# design.net
KiCad netlist of a schematic drawn in Altium Designer
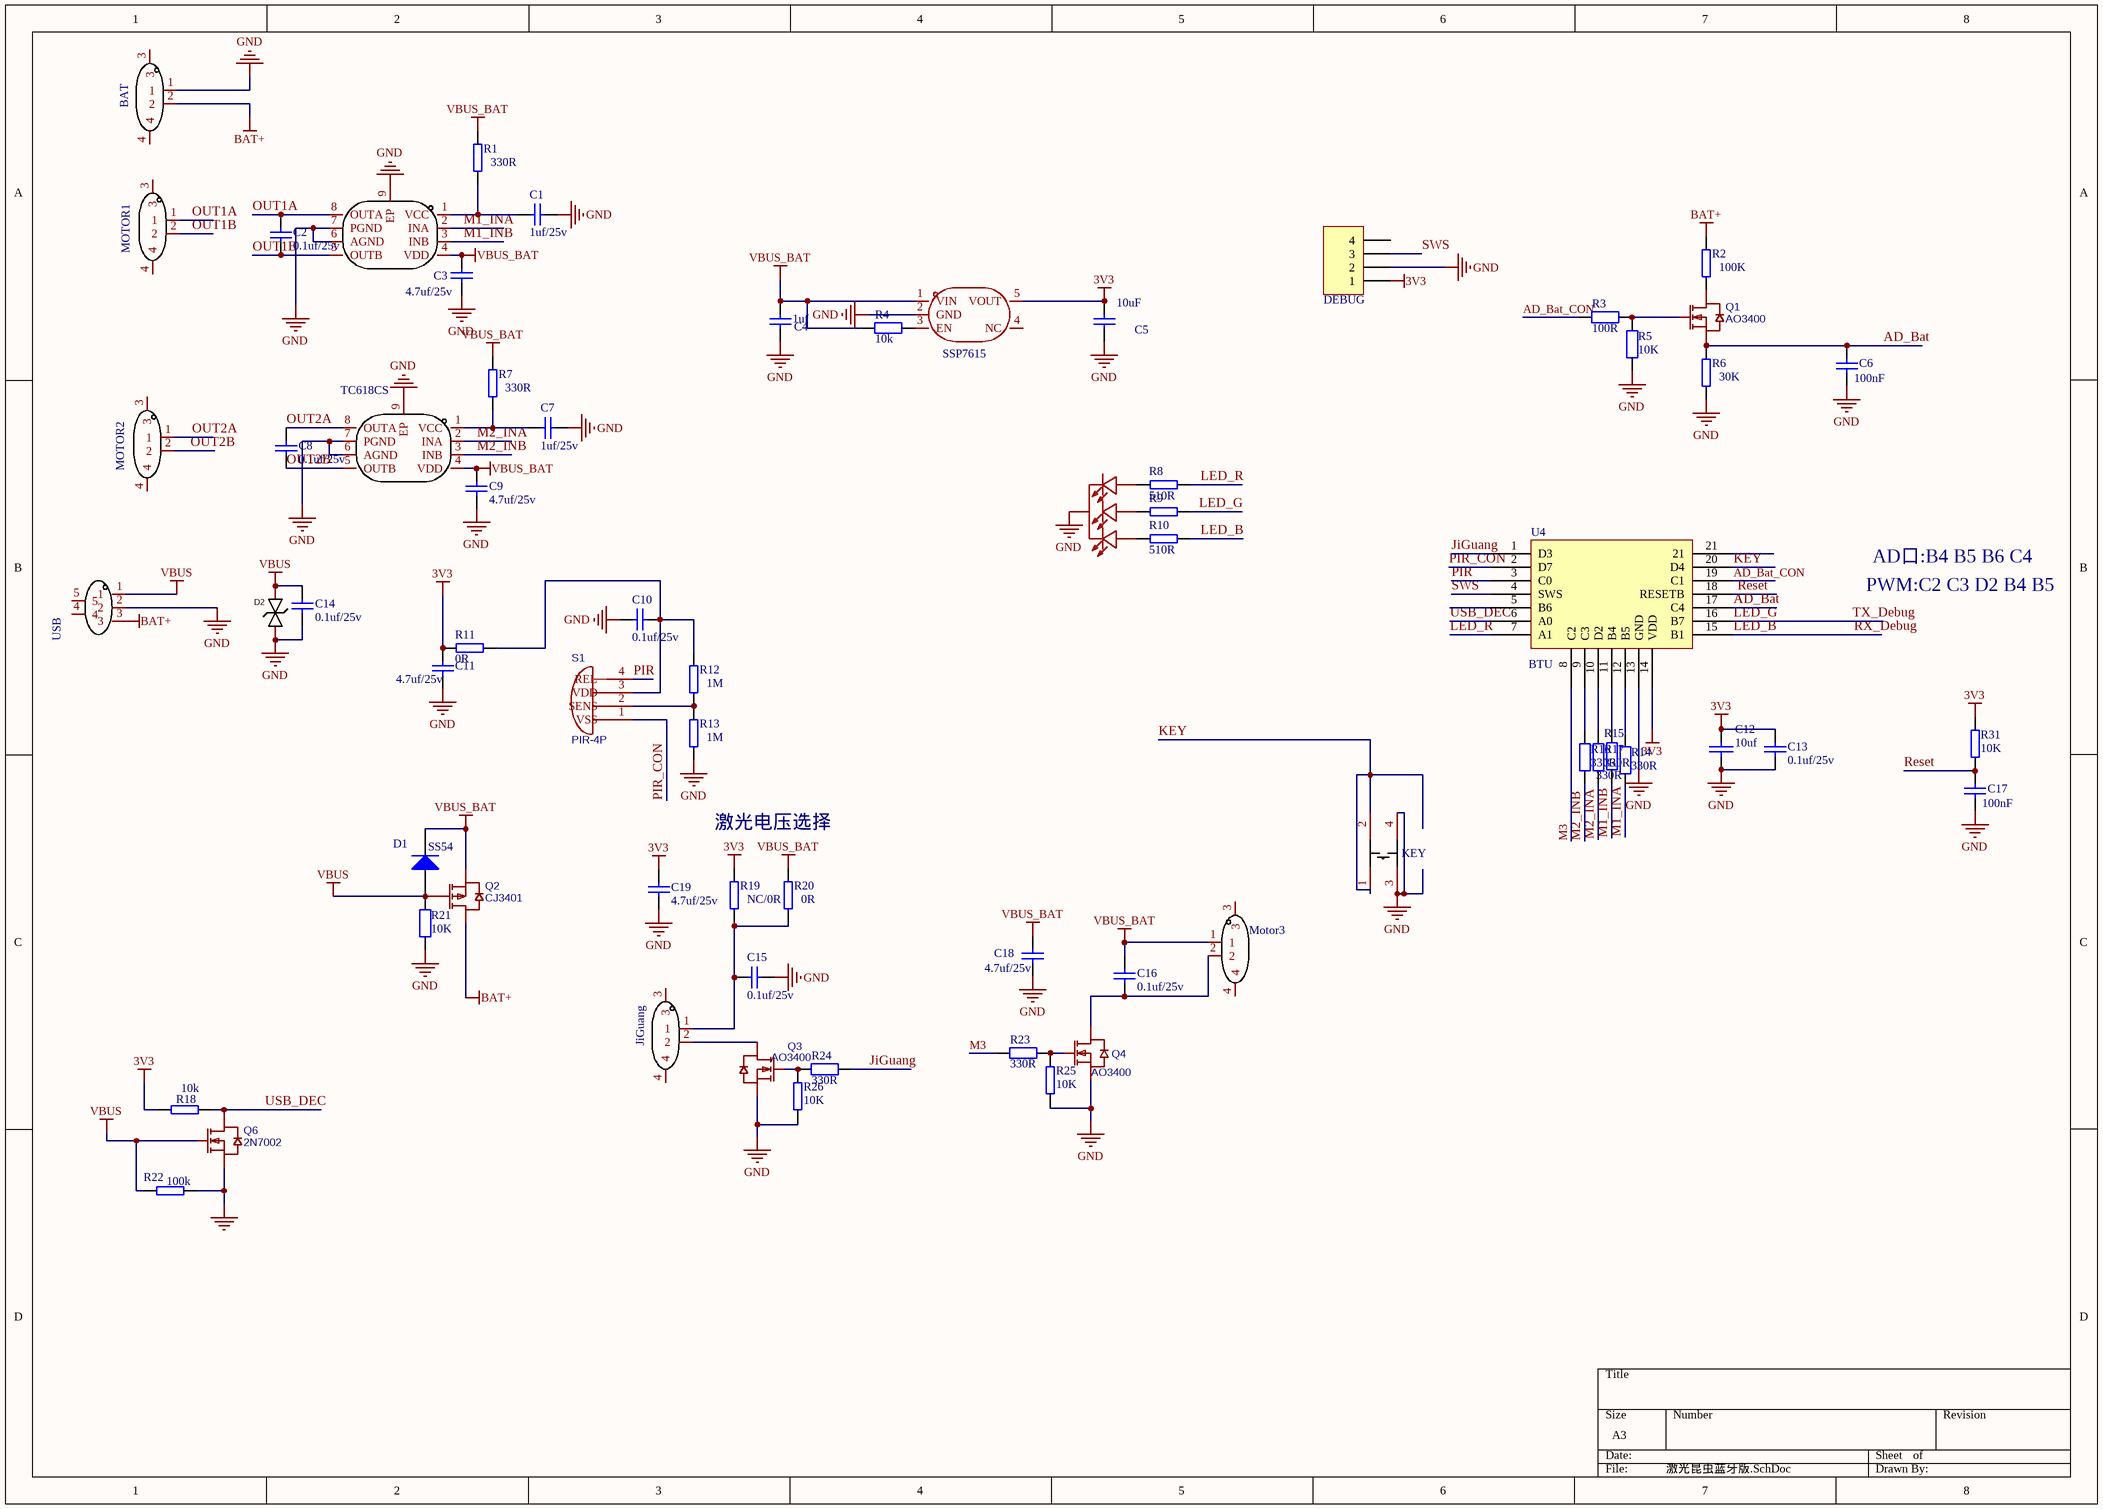
[diagram p0: 激光昆虫蓝牙版.SchDoc]

(export (version "E")
  (design (tool "Eeschema 10.0.6"))
  (components
    (comp (ref "C1")
      (value "1uf/25v")
      (footprint "0603_C")
      (description "Capacitor")
      (fields (field (name "PUBLISHER") "Altium Limited"))
      (libsource (lib "*") (part "Cap"))
    )
    (comp (ref "C2")
      (value "0.1uf/25v")
      (footprint "0603_C")
      (description "Capacitor")
      (fields (field (name "PUBLISHER") "Altium Limited"))
      (libsource (lib "*") (part "Cap"))
    )
    (comp (ref "C3")
      (value "4.7uf/25v")
      (footprint "0603_C")
      (description "Capacitor")
      (fields (field (name "PUBLISHER") "Altium Limited"))
      (libsource (lib "*") (part "Cap"))
    )
    (comp (ref "C4")
      (value "1uf")
      (footprint "0603_C")
      (description "无极电容")
      (libsource (lib "电容电阻电感保险") (part "Cap1"))
    )
    (comp (ref "C5")
      (value "10uF")
      (footprint "0603_C")
      (description "Capacitor")
      (fields (field (name "PUBLISHER") "Altium Limited"))
      (libsource (lib "*") (part "Cap"))
    )
    (comp (ref "C6") (value "100nF") (footprint "0603_C") (libsource (lib "DIY") (part "CAP")))
    (comp (ref "C7")
      (value "1uf/25v")
      (footprint "0603_C")
      (description "Capacitor")
      (fields (field (name "PUBLISHER") "Altium Limited"))
      (libsource (lib "*") (part "Cap"))
    )
    (comp (ref "C8")
      (value "0.1uf/25v")
      (footprint "0603_C")
      (description "Capacitor")
      (fields (field (name "PUBLISHER") "Altium Limited"))
      (libsource (lib "*") (part "Cap"))
    )
    (comp (ref "C9")
      (value "4.7uf/25v")
      (footprint "0603_C")
      (description "Capacitor")
      (fields (field (name "PUBLISHER") "Altium Limited"))
      (libsource (lib "*") (part "Cap"))
    )
    (comp (ref "C10")
      (value "0.1uf/25v")
      (footprint "0603_C")
      (description "Capacitor")
      (fields (field (name "PUBLISHER") "Altium Limited"))
      (libsource (lib "*") (part "Cap"))
    )
    (comp (ref "C11")
      (value "4.7uf/25v")
      (footprint "0603_C")
      (description "Capacitor")
      (fields (field (name "PUBLISHER") "Altium Limited"))
      (libsource (lib "*") (part "Cap"))
    )
    (comp (ref "C12")
      (value "10uf")
      (footprint "0603_c")
      (description "C-?-K-0603")
      (libsource (lib "HJ_AD_SchLib") (part "C-0603"))
    )
    (comp (ref "C13")
      (value "0.1uf/25v")
      (footprint "0603_C")
      (description "Capacitor")
      (fields (field (name "PUBLISHER") "Altium Limited"))
      (libsource (lib "*") (part "Cap"))
    )
    (comp (ref "C14")
      (value "0.1uf/25v")
      (footprint "0603_C")
      (description "Capacitor")
      (fields (field (name "PUBLISHER") "Altium Limited"))
      (libsource (lib "*") (part "Cap"))
    )
    (comp (ref "C15")
      (value "0.1uf/25v")
      (footprint "0603_C")
      (description "Capacitor")
      (fields (field (name "PUBLISHER") "Altium Limited"))
      (libsource (lib "*") (part "Cap"))
    )
    (comp (ref "C16")
      (value "0.1uf/25v")
      (footprint "0603_C")
      (description "Capacitor")
      (fields (field (name "PUBLISHER") "Altium Limited"))
      (libsource (lib "*") (part "Cap"))
    )
    (comp (ref "C17") (value "100nF") (footprint "0603_C") (libsource (lib "DIY") (part "CAP")))
    (comp (ref "C18")
      (value "4.7uf/25v")
      (footprint "0603_C")
      (description "Capacitor")
      (fields (field (name "PUBLISHER") "Altium Limited"))
      (libsource (lib "*") (part "Cap"))
    )
    (comp (ref "C19")
      (value "4.7uf/25v")
      (footprint "0603_C")
      (description "Capacitor")
      (fields (field (name "PUBLISHER") "Altium Limited"))
      (libsource (lib "*") (part "Cap"))
    )
    (comp (ref "CN1")
      (value "BAT")
      (footprint "CONN-SMD_2.0-2PLT")
      (fields (field (name "MANUFACTURER PART") "HC-1.25-2PLT"))
      (libsource (lib "altium-import") (part "root_0_mirrored_HC-1.25-2PLT_"))
    )
    (comp (ref "CN2")
      (value "MOTOR1")
      (footprint "SMD_HC-1.25-2PLT")
      (fields (field (name "MANUFACTURER PART") "HC-1.25-2PLT"))
      (libsource (lib "altium-import") (part "root_0_mirrored_HC-1.25-2PLT_"))
    )
    (comp (ref "CN3")
      (value "MOTOR2")
      (footprint "SMD_HC-1.25-2PLT")
      (fields (field (name "MANUFACTURER PART") "HC-1.25-2PLT"))
      (libsource (lib "altium-import") (part "root_0_mirrored_HC-1.25-2PLT_"))
    )
    (comp (ref "CN4")
      (value "USB")
      (footprint "SMD_HC-1.25-3PLT")
      (fields (field (name "MANUFACTURER PART") "HC-1.25-3PLT"))
      (libsource (lib "altium-import") (part "root_0_mirrored_HC-1.25-3PLT_"))
    )
    (comp (ref "CN5")
      (value "Motor3")
      (footprint "SMD_HC-1.25-2PLT")
      (fields (field (name "MANUFACTURER PART") "HC-1.25-2PLT"))
      (libsource (lib "altium-import") (part "root_0_HC-1.25-2PLT_"))
    )
    (comp (ref "CN6")
      (value "JiGuang")
      (footprint "SMD_HC-1.25-2PLT")
      (fields (field (name "MANUFACTURER PART") "HC-1.25-2PLT"))
      (libsource (lib "altium-import") (part "root_0_mirrored_HC-1.25-2PLT_"))
    )
    (comp (ref "D1")
      (value "SS54")
      (footprint "SMA")
      (description "High Conductance Fast Diode")
      (fields (field (name "PUBLISHER") "Altium Limited"))
      (libsource (lib "Miscellaneous Devices") (part "Diode 1N4148"))
    )
    (comp (ref "D2")
      (value "SMF6.0CA")
      (footprint "SOD-123 双向")
      (fields (field (name "MANUFACTURER PART") "SMF5.0CA"))
      (libsource (lib "altium-import") (part "root_1_SMF5.0CA_C726939_"))
    )
    (comp (ref "K1")
      (value "KEY")
      (footprint "KEY_SMD_4P")
      (fields (field (name "MANUFACTURER PART") "TS-1002S-05026C"))
      (libsource (lib "altium-import") (part "root_1_TS-1002S-05026C_"))
    )
    (comp (ref "LED1")
      (value "tj-s1615cy6tglccsrgb-a5")
      (footprint "LED-ARRAY-SMD_4P-L1.6-W1.5-BL-FD")
      (fields (field (name "MANUFACTURERPART") "TJ-S1615CY6TGLCCSRGB-A5"))
      (libsource (lib "altium-import") (part "root_0_tj-s1615cy6tglccsrgb-a5_"))
    )
    (comp (ref "P1")
      (value "DEBUG")
      (footprint "SIP3-2.54")
      (description "Header, 4-Pin")
      (fields (field (name "PUBLISHER") "Altium Limited"))
      (libsource (lib "Miscellaneous Connectors") (part "Header 4"))
    )
    (comp (ref "Q1")
      (value "AO3400")
      (footprint "SOT-23")
      (fields
        (field (name "BOM_SUPPLIER PART") "C2890442")
        (field (name "BOM_MANUFACTURER PART") "JMTL3400A")
        (field (name "CONTRIBUTOR") "LCSC")
      )
      (libsource (lib "altium-import") (part "root_0_JMTL3400A_"))
    )
    (comp (ref "Q2")
      (value "CJ3401")
      (footprint "SOT-23")
      (fields (field (name "BOM_SUPPLIER PART") "C13799"))
      (libsource (lib "altium-import") (part "root_2_mirrored_CJ3401_"))
    )
    (comp (ref "Q3")
      (value "AO3400")
      (footprint "SOT-23")
      (fields
        (field (name "BOM_SUPPLIER PART") "C2890442")
        (field (name "BOM_MANUFACTURER PART") "JMTL3400A")
        (field (name "CONTRIBUTOR") "LCSC")
      )
      (libsource (lib "altium-import") (part "root_0_mirrored_JMTL3400A_"))
    )
    (comp (ref "Q4")
      (value "AO3400")
      (footprint "SOT-23")
      (fields
        (field (name "BOM_SUPPLIER PART") "C2890442")
        (field (name "BOM_MANUFACTURER PART") "JMTL3400A")
        (field (name "CONTRIBUTOR") "LCSC")
      )
      (libsource (lib "altium-import") (part "root_0_JMTL3400A_"))
    )
    (comp (ref "Q6")
      (value "2N7002")
      (footprint "SOT-23")
      (fields
        (field (name "BOM_SUPPLIER PART") "C2890442")
        (field (name "BOM_MANUFACTURER PART") "JMTL3400A")
        (field (name "CONTRIBUTOR") "LCSC")
      )
      (libsource (lib "altium-import") (part "root_0_JMTL3400A_"))
    )
    (comp (ref "R1") (value "330R") (footprint "0603_R") (libsource (lib "DIY") (part "RES")))
    (comp (ref "R2") (value "100K") (footprint "0603_R") (libsource (lib "DIY") (part "RES")))
    (comp (ref "R3")
      (value "100R")
      (footprint "0603_r")
      (description "Resistor")
      (fields (field (name "PUBLISHER") "Altium Limited"))
      (libsource (lib "*") (part "Res2"))
    )
    (comp (ref "R4")
      (value "10k")
      (footprint "0603_R")
      (description "Resistor")
      (fields (field (name "PUBLISHER") "Altium Limited"))
      (libsource (lib "") (part "Res2_1"))
    )
    (comp (ref "R5")
      (value "10K")
      (footprint "0603_r")
      (description "Resistor")
      (fields (field (name "PUBLISHER") "Altium Limited"))
      (libsource (lib "") (part "Res2_1"))
    )
    (comp (ref "R6") (value "30K") (footprint "0603_R") (libsource (lib "DIY") (part "RES")))
    (comp (ref "R7") (value "330R") (footprint "0603_R") (libsource (lib "DIY") (part "RES")))
    (comp (ref "R8") (value "510R") (footprint "0603_R") (libsource (lib "DIY") (part "RES")))
    (comp (ref "R9") (value "510R") (footprint "0603_R") (libsource (lib "DIY") (part "RES")))
    (comp (ref "R10") (value "510R") (footprint "0603_R") (libsource (lib "DIY") (part "RES")))
    (comp (ref "R11") (value "0R") (footprint "0603_R") (libsource (lib "DIY") (part "RES")))
    (comp (ref "R12") (value "1M") (footprint "0603_R") (libsource (lib "DIY") (part "RES")))
    (comp (ref "R13") (value "1M") (footprint "0603_R") (libsource (lib "DIY") (part "RES")))
    (comp (ref "R14")
      (value "330R")
      (footprint "0603_R")
      (description "Resistor")
      (fields (field (name "PUBLISHER") "Altium Limited"))
      (libsource (lib "*") (part "Res2"))
    )
    (comp (ref "R15")
      (value "330R")
      (footprint "0603_R")
      (description "Resistor")
      (fields (field (name "PUBLISHER") "Altium Limited"))
      (libsource (lib "*") (part "Res2"))
    )
    (comp (ref "R16")
      (value "330R")
      (footprint "0603_R")
      (description "Resistor")
      (fields (field (name "PUBLISHER") "Altium Limited"))
      (libsource (lib "*") (part "Res2"))
    )
    (comp (ref "R17")
      (value "330R")
      (footprint "0603_R")
      (description "Resistor")
      (fields (field (name "PUBLISHER") "Altium Limited"))
      (libsource (lib "*") (part "Res2"))
    )
    (comp (ref "R18") (value "10k") (footprint "0603_R") (libsource (lib "DIY") (part "RES")))
    (comp (ref "R19") (value "NC/0R") (footprint "0603_R") (libsource (lib "DIY") (part "RES")))
    (comp (ref "R20") (value "0R") (footprint "0603_R") (libsource (lib "DIY") (part "RES")))
    (comp (ref "R21")
      (value "10K")
      (footprint "0603_R")
      (description "Resistor")
      (fields (field (name "PUBLISHER") "Altium Limited"))
      (libsource (lib "") (part "Res2_2"))
    )
    (comp (ref "R22") (value "100k") (footprint "0603_R") (libsource (lib "DIY") (part "RES")))
    (comp (ref "R23")
      (value "330R")
      (footprint "0603_R")
      (description "Resistor")
      (fields (field (name "PUBLISHER") "Altium Limited"))
      (libsource (lib "") (part "Res2_3"))
    )
    (comp (ref "R24")
      (value "330R")
      (footprint "0603_R")
      (description "Resistor")
      (fields (field (name "PUBLISHER") "Altium Limited"))
      (libsource (lib "") (part "Res2_2"))
    )
    (comp (ref "R25") (value "10K") (footprint "0603_R") (libsource (lib "DIY") (part "RES")))
    (comp (ref "R26") (value "10K") (footprint "0603_R") (libsource (lib "DIY") (part "RES")))
    (comp (ref "R31") (value "10K") (footprint "0603_R") (libsource (lib "DIY") (part "RES")))
    (comp (ref "S1")
      (value "PIR-4P")
      (footprint "PIR-D-4P")
      (fields (field (name "BOM_MANUFACTURER PART") "RE200B-P") (field (name "BOM_SUPPLIER PART") "C81765"))
      (libsource (lib "MyLib") (part "PIR-4P"))
    )
    (comp (ref "U1")
      (value "TC618CS")
      (footprint "ESOP-8")
      (libsource (lib "altium-import") (part "root_0_mirrored_TC618CS_"))
    )
    (comp (ref "U2")
      (value "SSP7615")
      (footprint "SOT-23-5")
      (libsource (lib "altium-import") (part "root_0_SSP7615-33M5R_"))
    )
    (comp (ref "U3")
      (value "TC618CS")
      (footprint "ESOP-8")
      (libsource (lib "altium-import") (part "root_0_mirrored_TC618CS_"))
    )
    (comp (ref "U4") (value "BTU") (footprint "BTU") (libsource (lib "MyLib") (part "BTU")))
  )
  (nets
    (net (code "1") (name "/AD_Bat") (class "Default")
      (node (ref "C6") (pin "2") (pintype "passive"))
      (node (ref "Q1") (pin "2") (pinfunction "S_2") (pintype "passive"))
      (node (ref "R6") (pin "1") (pinfunction "1_1") (pintype "passive"))
      (node (ref "U4") (pin "17") (pinfunction "C4_17") (pintype "passive"))
    )
    (net (code "2") (name "/AD_Bat_CON") (class "Default")
      (node (ref "R3") (pin "2") (pinfunction "2_2") (pintype "passive"))
      (node (ref "U4") (pin "19") (pinfunction "C1_19") (pintype "passive"))
    )
    (net (code "3") (name "/JiGuang") (class "Default")
      (node (ref "R24") (pin "2") (pinfunction "2_2") (pintype "passive"))
      (node (ref "U4") (pin "1") (pinfunction "D3_1") (pintype "passive"))
    )
    (net (code "4") (name "/KEY") (class "Default")
      (node (ref "K1") (pin "1") (pinfunction "1_1") (pintype "passive"))
      (node (ref "K1") (pin "2") (pinfunction "2_2") (pintype "passive"))
      (node (ref "U4") (pin "20") (pinfunction "D4_20") (pintype "passive"))
    )
    (net (code "5") (name "/LED_B") (class "Default")
      (node (ref "R10") (pin "1") (pinfunction "1_1") (pintype "passive"))
      (node (ref "U4") (pin "15") (pinfunction "B1_15") (pintype "passive"))
    )
    (net (code "6") (name "/LED_G") (class "Default")
      (node (ref "R9") (pin "1") (pinfunction "1_1") (pintype "passive"))
      (node (ref "U4") (pin "16") (pinfunction "B7_16") (pintype "passive"))
    )
    (net (code "7") (name "/LED_R") (class "Default")
      (node (ref "R8") (pin "1") (pinfunction "1_1") (pintype "passive"))
      (node (ref "U4") (pin "7") (pinfunction "A1_7") (pintype "passive"))
    )
    (net (code "8") (name "/M1_INA") (class "Default")
      (node (ref "R14") (pin "2") (pinfunction "2_2") (pintype "passive"))
      (node (ref "U1") (pin "2") (pinfunction "INA_2") (pintype "passive"))
    )
    (net (code "9") (name "/M1_INB") (class "Default")
      (node (ref "R15") (pin "2") (pinfunction "2_2") (pintype "passive"))
      (node (ref "U1") (pin "3") (pinfunction "INB_3") (pintype "passive"))
    )
    (net (code "10") (name "/M2_INA") (class "Default")
      (node (ref "R17") (pin "2") (pinfunction "2_2") (pintype "passive"))
      (node (ref "U3") (pin "2") (pinfunction "INA_2") (pintype "passive"))
    )
    (net (code "11") (name "/M2_INB") (class "Default")
      (node (ref "R16") (pin "2") (pinfunction "2_2") (pintype "passive"))
      (node (ref "U3") (pin "3") (pinfunction "INB_3") (pintype "passive"))
    )
    (net (code "12") (name "/M3") (class "Default")
      (node (ref "R23") (pin "2") (pinfunction "2_2") (pintype "passive"))
      (node (ref "U4") (pin "8") (pinfunction "C2_8") (pintype "passive"))
    )
    (net (code "13") (name "/OUT1A") (class "Default")
      (node (ref "C2") (pin "1") (pinfunction "1_1") (pintype "passive"))
      (node (ref "CN2") (pin "1") (pinfunction "1_1") (pintype "passive"))
      (node (ref "U1") (pin "8") (pinfunction "OUTA_8") (pintype "passive"))
    )
    (net (code "14") (name "/OUT1B") (class "Default")
      (node (ref "C2") (pin "2") (pinfunction "2_2") (pintype "passive"))
      (node (ref "CN2") (pin "2") (pinfunction "2_2") (pintype "passive"))
      (node (ref "U1") (pin "5") (pinfunction "OUTB_5") (pintype "passive"))
    )
    (net (code "15") (name "/OUT2A") (class "Default")
      (node (ref "C8") (pin "1") (pinfunction "1_1") (pintype "passive"))
      (node (ref "CN3") (pin "1") (pinfunction "1_1") (pintype "passive"))
      (node (ref "U3") (pin "8") (pinfunction "OUTA_8") (pintype "passive"))
    )
    (net (code "16") (name "/OUT2B") (class "Default")
      (node (ref "C8") (pin "2") (pinfunction "2_2") (pintype "passive"))
      (node (ref "CN3") (pin "2") (pinfunction "2_2") (pintype "passive"))
      (node (ref "U3") (pin "5") (pinfunction "OUTB_5") (pintype "passive"))
    )
    (net (code "17") (name "/PIR") (class "Default")
      (node (ref "S1") (pin "4") (pinfunction "REL_4") (pintype "passive"))
      (node (ref "U4") (pin "3") (pinfunction "C0_3") (pintype "passive"))
    )
    (net (code "18") (name "/PIR_CON") (class "Default")
      (node (ref "S1") (pin "1") (pinfunction "VSS_1") (pintype "passive"))
      (node (ref "U4") (pin "2") (pinfunction "D7_2") (pintype "passive"))
    )
    (net (code "19") (name "/Reset") (class "Default")
      (node (ref "C17") (pin "2") (pintype "passive"))
      (node (ref "R31") (pin "2") (pinfunction "2_2") (pintype "passive"))
      (node (ref "U4") (pin "18") (pinfunction "RESETB_18") (pintype "passive"))
    )
    (net (code "20") (name "/SWS") (class "Default")
      (node (ref "P1") (pin "3") (pinfunction "3_3") (pintype "passive"))
      (node (ref "U4") (pin "4") (pinfunction "SWS_4") (pintype "passive"))
    )
    (net (code "21") (name "/USB_DEC") (class "Default")
      (node (ref "Q6") (pin "3") (pinfunction "D_3") (pintype "passive"))
      (node (ref "R18") (pin "2") (pinfunction "2_2") (pintype "passive"))
      (node (ref "U4") (pin "6") (pinfunction "A0_6") (pintype "passive"))
    )
    (net (code "22") (name "3V3") (class "Default")
      (node (ref "C11") (pin "1") (pinfunction "1_1") (pintype "passive"))
      (node (ref "C12") (pin "2") (pinfunction "2_2") (pintype "passive"))
      (node (ref "C13") (pin "1") (pinfunction "1_1") (pintype "passive"))
      (node (ref "C19") (pin "1") (pinfunction "1_1") (pintype "passive"))
      (node (ref "C5") (pin "2") (pinfunction "2_2") (pintype "passive"))
      (node (ref "P1") (pin "1") (pinfunction "1_1") (pintype "passive"))
      (node (ref "R11") (pin "1") (pinfunction "1_1") (pintype "passive"))
      (node (ref "R18") (pin "1") (pinfunction "1_1") (pintype "passive"))
      (node (ref "R19") (pin "1") (pinfunction "1_1") (pintype "passive"))
      (node (ref "R31") (pin "1") (pinfunction "1_1") (pintype "passive"))
      (node (ref "U2") (pin "5") (pinfunction "VOUT_5") (pintype "passive"))
      (node (ref "U4") (pin "14") (pinfunction "VDD_14") (pintype "passive"))
    )
    (net (code "23") (name "BAT+") (class "Default")
      (node (ref "CN1") (pin "2") (pinfunction "2_2") (pintype "passive"))
      (node (ref "CN4") (pin "3") (pinfunction "3_3") (pintype "passive"))
      (node (ref "Q2") (pin "3") (pinfunction "D_3") (pintype "passive"))
      (node (ref "R2") (pin "1") (pinfunction "1_1") (pintype "passive"))
    )
    (net (code "24") (name "GND") (class "Default")
      (node (ref "C1") (pin "2") (pinfunction "2_2") (pintype "passive"))
      (node (ref "C10") (pin "2") (pinfunction "2_2") (pintype "passive"))
      (node (ref "C11") (pin "2") (pinfunction "2_2") (pintype "passive"))
      (node (ref "C12") (pin "1") (pinfunction "1_1") (pintype "passive"))
      (node (ref "C13") (pin "2") (pinfunction "2_2") (pintype "passive"))
      (node (ref "C14") (pin "2") (pinfunction "2_2") (pintype "passive"))
      (node (ref "C15") (pin "1") (pinfunction "1_1") (pintype "passive"))
      (node (ref "C17") (pin "1") (pintype "passive"))
      (node (ref "C18") (pin "1") (pinfunction "1_1") (pintype "passive"))
      (node (ref "C19") (pin "2") (pinfunction "2_2") (pintype "passive"))
      (node (ref "C3") (pin "2") (pinfunction "2_2") (pintype "passive"))
      (node (ref "C4") (pin "1") (pinfunction "1_1") (pintype "passive"))
      (node (ref "C5") (pin "1") (pinfunction "1_1") (pintype "passive"))
      (node (ref "C6") (pin "1") (pintype "passive"))
      (node (ref "C7") (pin "2") (pinfunction "2_2") (pintype "passive"))
      (node (ref "C9") (pin "2") (pinfunction "2_2") (pintype "passive"))
      (node (ref "CN1") (pin "1") (pinfunction "1_1") (pintype "passive"))
      (node (ref "CN4") (pin "2") (pinfunction "2_2") (pintype "passive"))
      (node (ref "D2") (pin "1") (pinfunction "1_1") (pintype "passive"))
      (node (ref "K1") (pin "3") (pinfunction "3_3") (pintype "passive"))
      (node (ref "K1") (pin "4") (pinfunction "4_4") (pintype "passive"))
      (node (ref "LED1") (pin "1") (pinfunction "C_1") (pintype "passive"))
      (node (ref "P1") (pin "2") (pinfunction "2_2") (pintype "passive"))
      (node (ref "Q3") (pin "2") (pinfunction "S_2") (pintype "passive"))
      (node (ref "Q4") (pin "2") (pinfunction "S_2") (pintype "passive"))
      (node (ref "Q6") (pin "2") (pinfunction "S_2") (pintype "passive"))
      (node (ref "R13") (pin "2") (pinfunction "2_2") (pintype "passive"))
      (node (ref "R21") (pin "1") (pinfunction "1_1") (pintype "passive"))
      (node (ref "R22") (pin "2") (pinfunction "2_2") (pintype "passive"))
      (node (ref "R25") (pin "1") (pinfunction "1_1") (pintype "passive"))
      (node (ref "R26") (pin "1") (pinfunction "1_1") (pintype "passive"))
      (node (ref "R5") (pin "1") (pinfunction "1_1") (pintype "passive"))
      (node (ref "R6") (pin "2") (pinfunction "2_2") (pintype "passive"))
      (node (ref "U1") (pin "6") (pinfunction "AGND_6") (pintype "passive"))
      (node (ref "U1") (pin "7") (pinfunction "PGND_7") (pintype "passive"))
      (node (ref "U1") (pin "9") (pinfunction "EP_9") (pintype "passive"))
      (node (ref "U2") (pin "2") (pinfunction "GND_2") (pintype "passive"))
      (node (ref "U3") (pin "6") (pinfunction "AGND_6") (pintype "passive"))
      (node (ref "U3") (pin "7") (pinfunction "PGND_7") (pintype "passive"))
      (node (ref "U3") (pin "9") (pinfunction "EP_9") (pintype "passive"))
      (node (ref "U4") (pin "13") (pinfunction "GND_13") (pintype "passive"))
    )
    (net (code "25") (name "Net-(C15-Pad2)") (class "Default")
      (node (ref "C15") (pin "2") (pinfunction "2_2") (pintype "passive"))
      (node (ref "CN6") (pin "1") (pinfunction "1_1") (pintype "passive"))
      (node (ref "R19") (pin "2") (pinfunction "2_2") (pintype "passive"))
      (node (ref "R20") (pin "2") (pinfunction "2_2") (pintype "passive"))
    )
    (net (code "26") (name "Net-(LED1-B)") (class "Default")
      (node (ref "LED1") (pin "2") (pinfunction "B_2") (pintype "passive"))
      (node (ref "R10") (pin "2") (pinfunction "2_2") (pintype "passive"))
    )
    (net (code "27") (name "Net-(LED1-G)") (class "Default")
      (node (ref "LED1") (pin "3") (pinfunction "G_3") (pintype "passive"))
      (node (ref "R9") (pin "2") (pinfunction "2_2") (pintype "passive"))
    )
    (net (code "28") (name "Net-(LED1-R)") (class "Default")
      (node (ref "LED1") (pin "4") (pinfunction "R_4") (pintype "passive"))
      (node (ref "R8") (pin "2") (pinfunction "2_2") (pintype "passive"))
    )
    (net (code "29") (name "Net-(Q1-D)") (class "Default")
      (node (ref "Q1") (pin "3") (pinfunction "D_3") (pintype "passive"))
      (node (ref "R2") (pin "2") (pinfunction "2_2") (pintype "passive"))
    )
    (net (code "30") (name "Net-(Q1-G)") (class "Default")
      (node (ref "Q1") (pin "1") (pinfunction "G_1") (pintype "passive"))
      (node (ref "R3") (pin "1") (pinfunction "1_1") (pintype "passive"))
      (node (ref "R5") (pin "2") (pinfunction "2_2") (pintype "passive"))
    )
    (net (code "31") (name "Net-(Q3-D)") (class "Default")
      (node (ref "CN6") (pin "2") (pinfunction "2_2") (pintype "passive"))
      (node (ref "Q3") (pin "3") (pinfunction "D_3") (pintype "passive"))
    )
    (net (code "32") (name "Net-(Q3-G)") (class "Default")
      (node (ref "Q3") (pin "1") (pinfunction "G_1") (pintype "passive"))
      (node (ref "R24") (pin "1") (pinfunction "1_1") (pintype "passive"))
      (node (ref "R26") (pin "2") (pinfunction "2_2") (pintype "passive"))
    )
    (net (code "33") (name "Net-(Q4-D)") (class "Default")
      (node (ref "C16") (pin "1") (pinfunction "1_1") (pintype "passive"))
      (node (ref "CN5") (pin "2") (pinfunction "2_2") (pintype "passive"))
      (node (ref "Q4") (pin "3") (pinfunction "D_3") (pintype "passive"))
    )
    (net (code "34") (name "Net-(Q4-G)") (class "Default")
      (node (ref "Q4") (pin "1") (pinfunction "G_1") (pintype "passive"))
      (node (ref "R23") (pin "1") (pinfunction "1_1") (pintype "passive"))
      (node (ref "R25") (pin "2") (pinfunction "2_2") (pintype "passive"))
    )
    (net (code "35") (name "Net-(S1-SENS)") (class "Default")
      (node (ref "R12") (pin "2") (pinfunction "2_2") (pintype "passive"))
      (node (ref "R13") (pin "1") (pinfunction "1_1") (pintype "passive"))
      (node (ref "S1") (pin "2") (pinfunction "SENS_2") (pintype "passive"))
    )
    (net (code "36") (name "Net-(S1-VDD)") (class "Default")
      (node (ref "C10") (pin "1") (pinfunction "1_1") (pintype "passive"))
      (node (ref "R11") (pin "2") (pinfunction "2_2") (pintype "passive"))
      (node (ref "R12") (pin "1") (pinfunction "1_1") (pintype "passive"))
      (node (ref "S1") (pin "3") (pinfunction "VDD_3") (pintype "passive"))
    )
    (net (code "37") (name "Net-(U1-VCC)") (class "Default")
      (node (ref "C1") (pin "1") (pinfunction "1_1") (pintype "passive"))
      (node (ref "R1") (pin "2") (pinfunction "2_2") (pintype "passive"))
      (node (ref "U1") (pin "1") (pinfunction "VCC_1") (pintype "passive"))
    )
    (net (code "38") (name "Net-(U2-EN)") (class "Default")
      (node (ref "R4") (pin "2") (pinfunction "2_2") (pintype "passive"))
      (node (ref "U2") (pin "3") (pinfunction "EN_3") (pintype "passive"))
    )
    (net (code "39") (name "Net-(U3-VCC)") (class "Default")
      (node (ref "C7") (pin "1") (pinfunction "1_1") (pintype "passive"))
      (node (ref "R7") (pin "2") (pinfunction "2_2") (pintype "passive"))
      (node (ref "U3") (pin "1") (pinfunction "VCC_1") (pintype "passive"))
    )
    (net (code "40") (name "Net-(U4-B4)") (class "Default")
      (node (ref "R15") (pin "1") (pinfunction "1_1") (pintype "passive"))
      (node (ref "U4") (pin "11") (pinfunction "B4_11") (pintype "passive"))
    )
    (net (code "41") (name "Net-(U4-B5)") (class "Default")
      (node (ref "R14") (pin "1") (pinfunction "1_1") (pintype "passive"))
      (node (ref "U4") (pin "12") (pinfunction "B5_12") (pintype "passive"))
    )
    (net (code "42") (name "Net-(U4-C3)") (class "Default")
      (node (ref "R16") (pin "1") (pinfunction "1_1") (pintype "passive"))
      (node (ref "U4") (pin "9") (pinfunction "C3_9") (pintype "passive"))
    )
    (net (code "43") (name "Net-(U4-D2)") (class "Default")
      (node (ref "R17") (pin "1") (pinfunction "1_1") (pintype "passive"))
      (node (ref "U4") (pin "10") (pinfunction "D2_10") (pintype "passive"))
    )
    (net (code "44") (name "VBUS") (class "Default")
      (node (ref "C14") (pin "1") (pinfunction "1_1") (pintype "passive"))
      (node (ref "CN4") (pin "1") (pinfunction "1_1") (pintype "passive"))
      (node (ref "D1") (pin "1") (pinfunction "A_1") (pintype "passive"))
      (node (ref "D2") (pin "2") (pinfunction "2_2") (pintype "passive"))
      (node (ref "Q2") (pin "1") (pinfunction "G_1") (pintype "passive"))
      (node (ref "Q6") (pin "1") (pinfunction "G_1") (pintype "passive"))
      (node (ref "R21") (pin "2") (pinfunction "2_2") (pintype "passive"))
      (node (ref "R22") (pin "1") (pinfunction "1_1") (pintype "passive"))
    )
    (net (code "45") (name "VBUS_BAT") (class "Default")
      (node (ref "C16") (pin "2") (pinfunction "2_2") (pintype "passive"))
      (node (ref "C18") (pin "2") (pinfunction "2_2") (pintype "passive"))
      (node (ref "C3") (pin "1") (pinfunction "1_1") (pintype "passive"))
      (node (ref "C4") (pin "2") (pinfunction "2_2") (pintype "passive"))
      (node (ref "C9") (pin "1") (pinfunction "1_1") (pintype "passive"))
      (node (ref "CN5") (pin "1") (pinfunction "1_1") (pintype "passive"))
      (node (ref "D1") (pin "2") (pinfunction "K_2") (pintype "passive"))
      (node (ref "Q2") (pin "2") (pinfunction "S_2") (pintype "passive"))
      (node (ref "R1") (pin "1") (pinfunction "1_1") (pintype "passive"))
      (node (ref "R20") (pin "1") (pinfunction "1_1") (pintype "passive"))
      (node (ref "R4") (pin "1") (pinfunction "1_1") (pintype "passive"))
      (node (ref "R7") (pin "1") (pinfunction "1_1") (pintype "passive"))
      (node (ref "U1") (pin "4") (pinfunction "VDD_4") (pintype "passive"))
      (node (ref "U2") (pin "1") (pinfunction "VIN_1") (pintype "passive"))
      (node (ref "U3") (pin "4") (pinfunction "VDD_4") (pintype "passive"))
    )
    (net (code "46") (name "unconnected-(CN1-Pad3)") (class "Default")
      (node (ref "CN1") (pin "3") (pinfunction "3_3") (pintype "passive"))
    )
    (net (code "47") (name "unconnected-(CN1-Pad4)") (class "Default")
      (node (ref "CN1") (pin "4") (pinfunction "4_4") (pintype "passive"))
    )
    (net (code "48") (name "unconnected-(CN2-Pad3)") (class "Default")
      (node (ref "CN2") (pin "3") (pinfunction "3_3") (pintype "passive"))
    )
    (net (code "49") (name "unconnected-(CN2-Pad4)") (class "Default")
      (node (ref "CN2") (pin "4") (pinfunction "4_4") (pintype "passive"))
    )
    (net (code "50") (name "unconnected-(CN3-Pad3)") (class "Default")
      (node (ref "CN3") (pin "3") (pinfunction "3_3") (pintype "passive"))
    )
    (net (code "51") (name "unconnected-(CN3-Pad4)") (class "Default")
      (node (ref "CN3") (pin "4") (pinfunction "4_4") (pintype "passive"))
    )
    (net (code "52") (name "unconnected-(CN4-Pad4)") (class "Default")
      (node (ref "CN4") (pin "4") (pinfunction "4_4") (pintype "passive"))
    )
    (net (code "53") (name "unconnected-(CN4-Pad5)") (class "Default")
      (node (ref "CN4") (pin "5") (pinfunction "5_5") (pintype "passive"))
    )
    (net (code "54") (name "unconnected-(CN5-Pad3)") (class "Default")
      (node (ref "CN5") (pin "3") (pinfunction "3_3") (pintype "passive"))
    )
    (net (code "55") (name "unconnected-(CN5-Pad4)") (class "Default")
      (node (ref "CN5") (pin "4") (pinfunction "4_4") (pintype "passive"))
    )
    (net (code "56") (name "unconnected-(CN6-Pad3)") (class "Default")
      (node (ref "CN6") (pin "3") (pinfunction "3_3") (pintype "passive"))
    )
    (net (code "57") (name "unconnected-(CN6-Pad4)") (class "Default")
      (node (ref "CN6") (pin "4") (pinfunction "4_4") (pintype "passive"))
    )
    (net (code "58") (name "unconnected-(P1-Pad4)") (class "Default")
      (node (ref "P1") (pin "4") (pinfunction "4_4") (pintype "passive"))
    )
    (net (code "59") (name "unconnected-(U2-NC-Pad4)") (class "Default")
      (node (ref "U2") (pin "4") (pinfunction "NC_4") (pintype "passive"))
    )
    (net (code "60") (name "unconnected-(U4-B6-Pad5)") (class "Default")
      (node (ref "U4") (pin "5") (pinfunction "B6_5") (pintype "passive"))
    )
    (net (code "61") (name "unconnected-(U4-Pad21)") (class "Default")
      (node (ref "U4") (pin "21") (pinfunction "21_21") (pintype "passive"))
    )
  )
)
